# placa_eagle_1.net
KiCad netlist of a schematic drawn in EAGLE
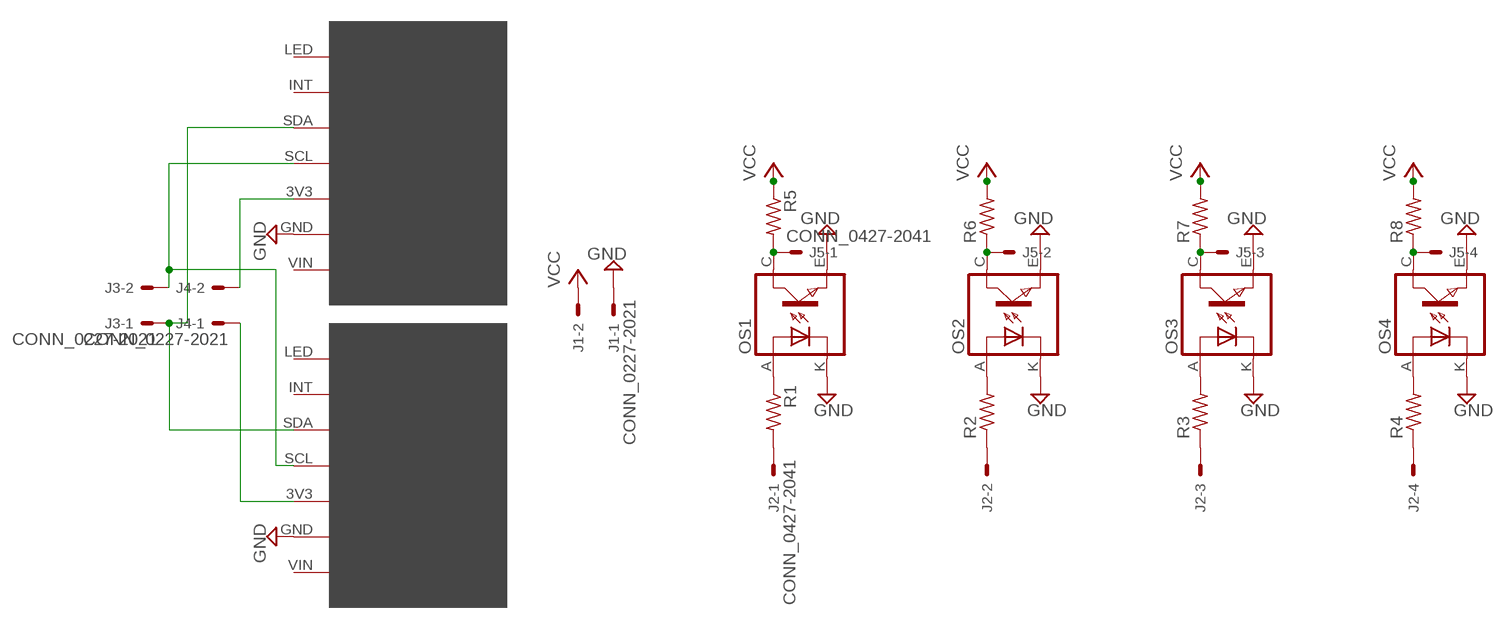
[diagram p0: schematic, sheet 1]

(export (version "E")
  (design (tool "Eeschema 10.0.6"))
  (components
    (comp (ref "J1")
      (value "CONN_0227-2021")
      (footprint "eagle-import:6410-02")
      (libsource (lib "eagle-import") (part "CONN_0227-2021"))
    )
    (comp (ref "J2")
      (value "CONN_0427-2041")
      (footprint "eagle-import:6410-04")
      (libsource (lib "eagle-import") (part "CONN_0427-2041"))
    )
    (comp (ref "J3")
      (value "CONN_0227-2021")
      (footprint "eagle-import:6410-02")
      (libsource (lib "eagle-import") (part "CONN_0227-2021"))
    )
    (comp (ref "J4")
      (value "CONN_0227-2021")
      (footprint "eagle-import:6410-02")
      (libsource (lib "eagle-import") (part "CONN_0227-2021"))
    )
    (comp (ref "J5")
      (value "CONN_0427-2041")
      (footprint "eagle-import:6410-04")
      (libsource (lib "eagle-import") (part "CONN_0427-2041"))
    )
    (comp (ref "OS1")
      (value "TCRT5000")
      (footprint "eagle-import:TCRT5000")
      (libsource (lib "eagle-import") (part "TCRT5000"))
    )
    (comp (ref "OS2")
      (value "TCRT5000")
      (footprint "eagle-import:TCRT5000")
      (libsource (lib "eagle-import") (part "TCRT5000"))
    )
    (comp (ref "OS3")
      (value "TCRT5000")
      (footprint "eagle-import:TCRT5000")
      (libsource (lib "eagle-import") (part "TCRT5000"))
    )
    (comp (ref "OS4")
      (value "TCRT5000")
      (footprint "eagle-import:TCRT5000")
      (libsource (lib "eagle-import") (part "TCRT5000"))
    )
    (comp (ref "R1")
      (value "R-US_0204/7")
      (footprint "eagle-import:0204_7")
      (libsource (lib "eagle-import") (part "R-US_0204/7"))
    )
    (comp (ref "R2")
      (value "R-US_0204/7")
      (footprint "eagle-import:0204_7")
      (libsource (lib "eagle-import") (part "R-US_0204/7"))
    )
    (comp (ref "R3")
      (value "R-US_0204/7")
      (footprint "eagle-import:0204_7")
      (libsource (lib "eagle-import") (part "R-US_0204/7"))
    )
    (comp (ref "R4")
      (value "R-US_0204/7")
      (footprint "eagle-import:0204_7")
      (libsource (lib "eagle-import") (part "R-US_0204/7"))
    )
    (comp (ref "R5")
      (value "R-US_0204/7")
      (footprint "eagle-import:0204_7")
      (libsource (lib "eagle-import") (part "R-US_0204/7"))
    )
    (comp (ref "R6")
      (value "R-US_0204/7")
      (footprint "eagle-import:0204_7")
      (libsource (lib "eagle-import") (part "R-US_0204/7"))
    )
    (comp (ref "R7")
      (value "R-US_0204/7")
      (footprint "eagle-import:0204_7")
      (libsource (lib "eagle-import") (part "R-US_0204/7"))
    )
    (comp (ref "R8")
      (value "R-US_0204/7")
      (footprint "eagle-import:0204_7")
      (libsource (lib "eagle-import") (part "R-US_0204/7"))
    )
    (comp (ref "TCS1")
      (value "TCS34725")
      (footprint "eagle-import:TCS34725")
      (libsource (lib "eagle-import") (part "TCS34725"))
    )
    (comp (ref "TCS2")
      (value "TCS34725")
      (footprint "eagle-import:TCS34725")
      (libsource (lib "eagle-import") (part "TCS34725"))
    )
  )
  (nets
    (net (code "1") (name "GND") (class "Default")
      (node (ref "J1") (pin "1") (pinfunction "S_1") (pintype "passive"))
      (node (ref "OS1") (pin "E") (pinfunction "EMITTER_E") (pintype "passive"))
      (node (ref "OS1") (pin "K") (pinfunction "CATHODE_K") (pintype "passive"))
      (node (ref "OS2") (pin "E") (pinfunction "EMITTER_E") (pintype "passive"))
      (node (ref "OS2") (pin "K") (pinfunction "CATHODE_K") (pintype "passive"))
      (node (ref "OS3") (pin "E") (pinfunction "EMITTER_E") (pintype "passive"))
      (node (ref "OS3") (pin "K") (pinfunction "CATHODE_K") (pintype "passive"))
      (node (ref "OS4") (pin "E") (pinfunction "EMITTER_E") (pintype "passive"))
      (node (ref "OS4") (pin "K") (pinfunction "CATHODE_K") (pintype "passive"))
      (node (ref "TCS1") (pin "GND") (pinfunction "GND_GND") (pintype "bidirectional"))
      (node (ref "TCS2") (pin "GND") (pinfunction "GND_GND") (pintype "bidirectional"))
    )
    (net (code "2") (name "Net-(J2A-S)") (class "Default")
      (node (ref "J2") (pin "1") (pinfunction "S_1") (pintype "passive"))
      (node (ref "R1") (pin "2") (pinfunction "2_2") (pintype "passive"))
    )
    (net (code "3") (name "Net-(J2B-S)") (class "Default")
      (node (ref "J2") (pin "2") (pinfunction "S_2") (pintype "passive"))
      (node (ref "R2") (pin "1") (pinfunction "1_1") (pintype "passive"))
    )
    (net (code "4") (name "Net-(J2C-S)") (class "Default")
      (node (ref "J2") (pin "3") (pinfunction "S_3") (pintype "passive"))
      (node (ref "R3") (pin "1") (pinfunction "1_1") (pintype "passive"))
    )
    (net (code "5") (name "Net-(J2D-S)") (class "Default")
      (node (ref "J2") (pin "4") (pinfunction "S_4") (pintype "passive"))
      (node (ref "R4") (pin "1") (pinfunction "1_1") (pintype "passive"))
    )
    (net (code "6") (name "Net-(J3A-S)") (class "Default")
      (node (ref "J3") (pin "1") (pinfunction "S_1") (pintype "passive"))
      (node (ref "TCS1") (pin "SDA") (pinfunction "SDA_SDA") (pintype "bidirectional"))
      (node (ref "TCS2") (pin "SDA") (pinfunction "SDA_SDA") (pintype "bidirectional"))
    )
    (net (code "7") (name "Net-(J3B-S)") (class "Default")
      (node (ref "J3") (pin "2") (pinfunction "S_2") (pintype "passive"))
      (node (ref "TCS1") (pin "SCL") (pinfunction "SCL_SCL") (pintype "bidirectional"))
      (node (ref "TCS2") (pin "SCL") (pinfunction "SCL_SCL") (pintype "bidirectional"))
    )
    (net (code "8") (name "Net-(J4A-S)") (class "Default")
      (node (ref "J4") (pin "1") (pinfunction "S_1") (pintype "passive"))
      (node (ref "TCS2") (pin "3V3") (pinfunction "3V3_3V3") (pintype "bidirectional"))
    )
    (net (code "9") (name "Net-(J4B-S)") (class "Default")
      (node (ref "J4") (pin "2") (pinfunction "S_2") (pintype "passive"))
      (node (ref "TCS1") (pin "3V3") (pinfunction "3V3_3V3") (pintype "bidirectional"))
    )
    (net (code "10") (name "Net-(J5A-S)") (class "Default")
      (node (ref "J5") (pin "1") (pinfunction "S_1") (pintype "passive"))
      (node (ref "OS1") (pin "C") (pinfunction "COLLECTOR_C") (pintype "passive"))
      (node (ref "R5") (pin "2") (pinfunction "2_2") (pintype "passive"))
    )
    (net (code "11") (name "Net-(J5B-S)") (class "Default")
      (node (ref "J5") (pin "2") (pinfunction "S_2") (pintype "passive"))
      (node (ref "OS2") (pin "C") (pinfunction "COLLECTOR_C") (pintype "passive"))
      (node (ref "R6") (pin "1") (pinfunction "1_1") (pintype "passive"))
    )
    (net (code "12") (name "Net-(J5C-S)") (class "Default")
      (node (ref "J5") (pin "3") (pinfunction "S_3") (pintype "passive"))
      (node (ref "OS3") (pin "C") (pinfunction "COLLECTOR_C") (pintype "passive"))
      (node (ref "R7") (pin "1") (pinfunction "1_1") (pintype "passive"))
    )
    (net (code "13") (name "Net-(J5D-S)") (class "Default")
      (node (ref "J5") (pin "4") (pinfunction "S_4") (pintype "passive"))
      (node (ref "OS4") (pin "C") (pinfunction "COLLECTOR_C") (pintype "passive"))
      (node (ref "R8") (pin "1") (pinfunction "1_1") (pintype "passive"))
    )
    (net (code "14") (name "Net-(OS1-ANODE)") (class "Default")
      (node (ref "OS1") (pin "A") (pinfunction "ANODE_A") (pintype "passive"))
      (node (ref "R1") (pin "1") (pinfunction "1_1") (pintype "passive"))
    )
    (net (code "15") (name "Net-(OS2-ANODE)") (class "Default")
      (node (ref "OS2") (pin "A") (pinfunction "ANODE_A") (pintype "passive"))
      (node (ref "R2") (pin "2") (pinfunction "2_2") (pintype "passive"))
    )
    (net (code "16") (name "Net-(OS3-ANODE)") (class "Default")
      (node (ref "OS3") (pin "A") (pinfunction "ANODE_A") (pintype "passive"))
      (node (ref "R3") (pin "2") (pinfunction "2_2") (pintype "passive"))
    )
    (net (code "17") (name "Net-(OS4-ANODE)") (class "Default")
      (node (ref "OS4") (pin "A") (pinfunction "ANODE_A") (pintype "passive"))
      (node (ref "R4") (pin "2") (pinfunction "2_2") (pintype "passive"))
    )
    (net (code "18") (name "VCC") (class "Default")
      (node (ref "J1") (pin "2") (pinfunction "S_2") (pintype "passive"))
      (node (ref "R5") (pin "1") (pinfunction "1_1") (pintype "passive"))
      (node (ref "R6") (pin "2") (pinfunction "2_2") (pintype "passive"))
      (node (ref "R7") (pin "2") (pinfunction "2_2") (pintype "passive"))
      (node (ref "R8") (pin "2") (pinfunction "2_2") (pintype "passive"))
    )
    (net (code "19") (name "unconnected-(TCS1-PadINT)") (class "Default")
      (node (ref "TCS1") (pin "INT") (pinfunction "INT_INT") (pintype "bidirectional"))
    )
    (net (code "20") (name "unconnected-(TCS1-PadLED)") (class "Default")
      (node (ref "TCS1") (pin "LED") (pinfunction "LED_LED") (pintype "bidirectional"))
    )
    (net (code "21") (name "unconnected-(TCS1-PadVIN)") (class "Default")
      (node (ref "TCS1") (pin "VIN") (pinfunction "VIN_VIN") (pintype "bidirectional"))
    )
    (net (code "22") (name "unconnected-(TCS2-PadINT)") (class "Default")
      (node (ref "TCS2") (pin "INT") (pinfunction "INT_INT") (pintype "bidirectional"))
    )
    (net (code "23") (name "unconnected-(TCS2-PadLED)") (class "Default")
      (node (ref "TCS2") (pin "LED") (pinfunction "LED_LED") (pintype "bidirectional"))
    )
    (net (code "24") (name "unconnected-(TCS2-PadVIN)") (class "Default")
      (node (ref "TCS2") (pin "VIN") (pinfunction "VIN_VIN") (pintype "bidirectional"))
    )
  )
)
